# SkyKontrol-2BR.net
KiCad netlist of a schematic drawn in EAGLE
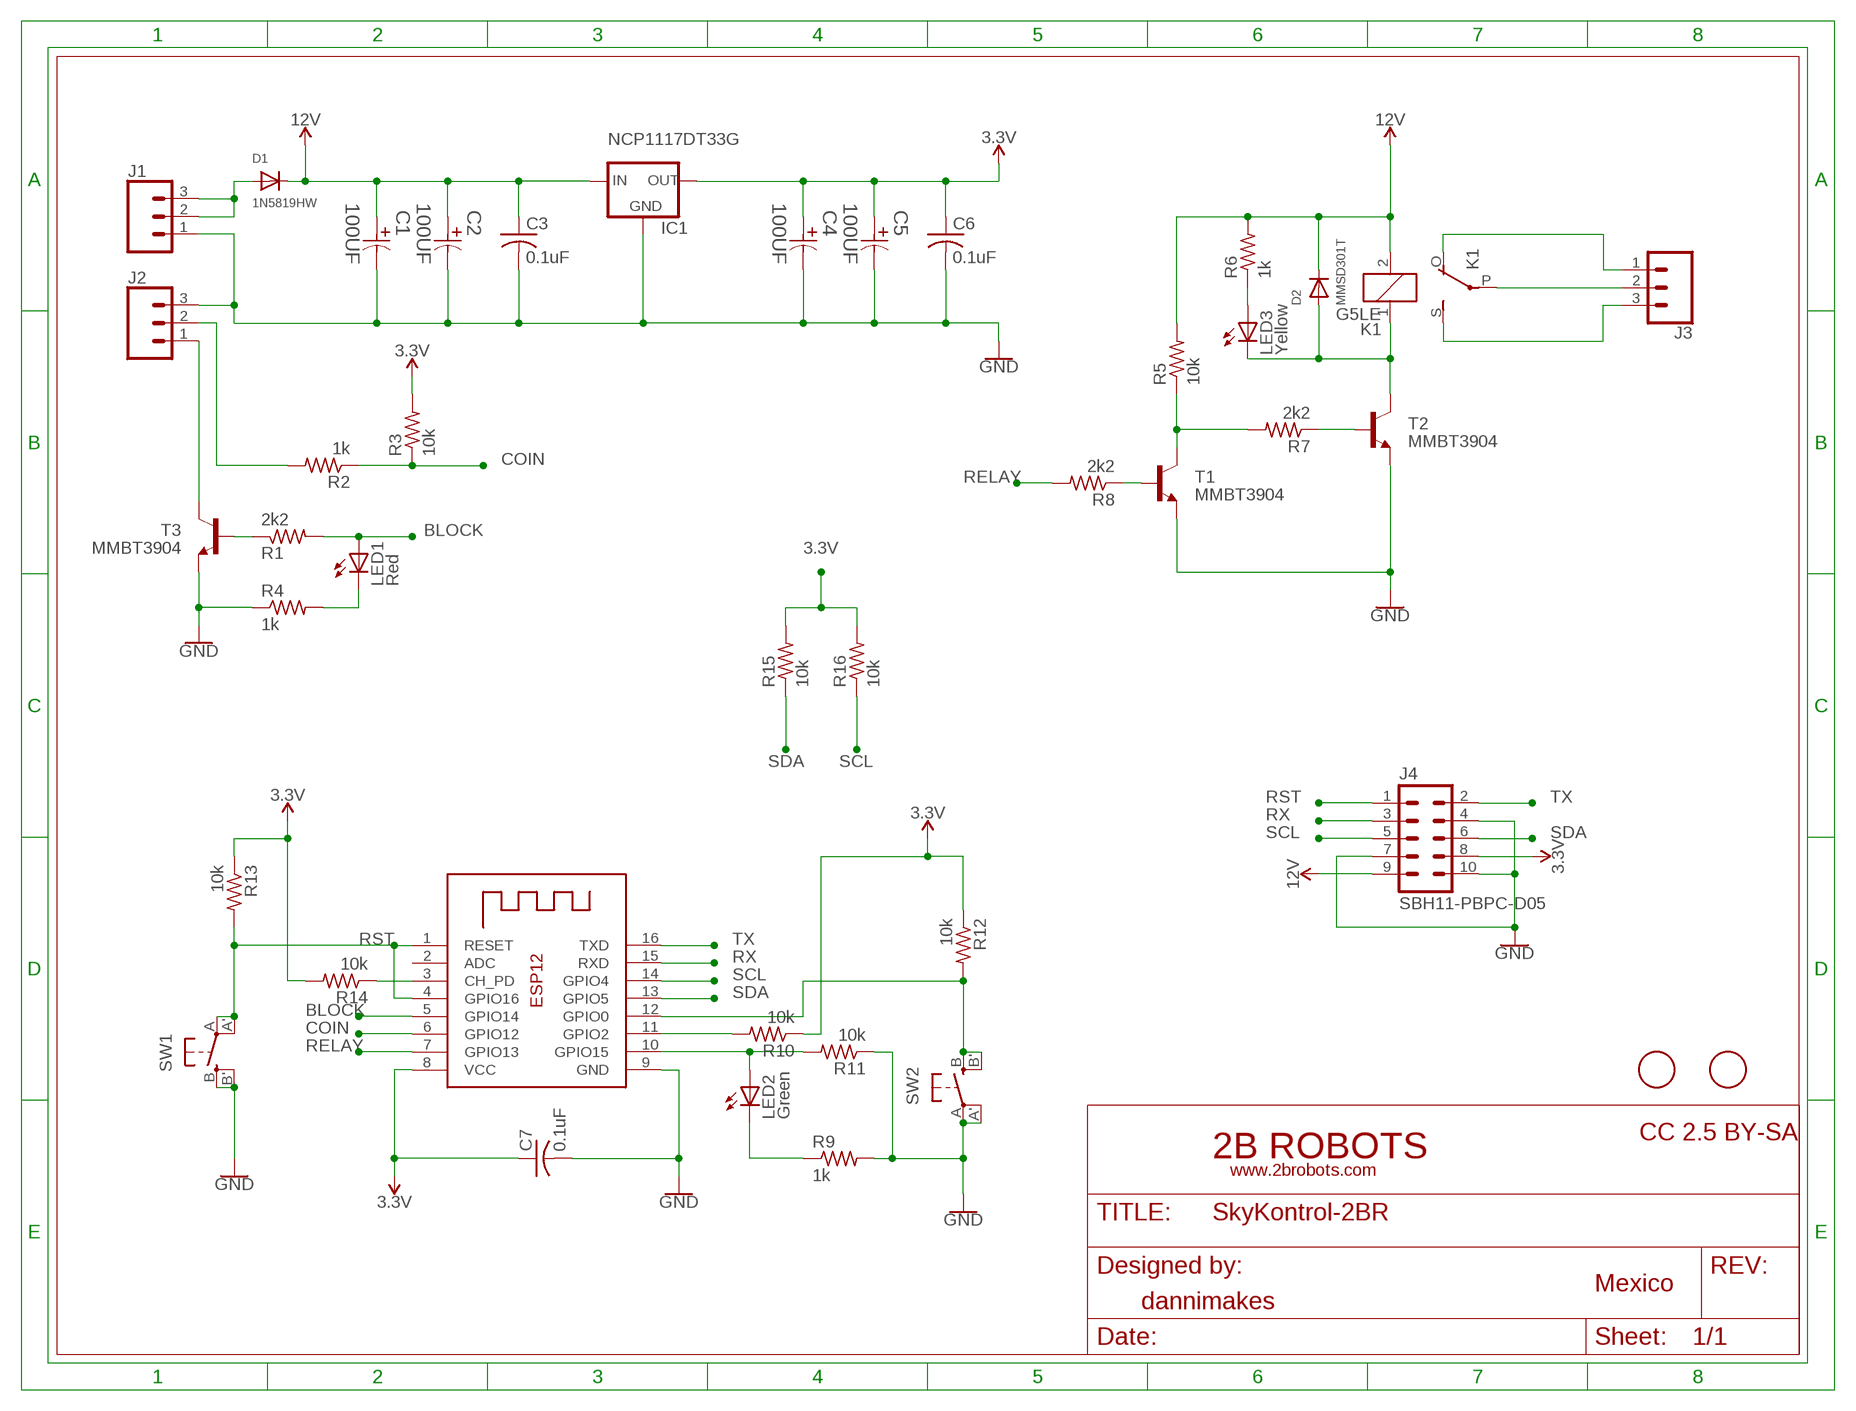
[diagram p0: schematic, sheet 1]

(export (version "E")
  (design (tool "Eeschema 10.0.6"))
  (components
    (comp (ref "C1")
      (value "100UF")
      (footprint "eagle-import:CAPAE660X800N")
      (fields (field (name "MPN") "EEE-HA1E101XP") (field (name "TOLERANCE") "±20 %"))
      (libsource (lib "eagle-import") (part "EEE--CASE-D8HA1E101XP"))
    )
    (comp (ref "C2")
      (value "100UF")
      (footprint "eagle-import:CAPAE660X800N")
      (fields (field (name "MPN") "EEE-HA1E101XP") (field (name "TOLERANCE") "±20 %"))
      (libsource (lib "eagle-import") (part "EEE--CASE-D8HA1E101XP"))
    )
    (comp (ref "C3")
      (value "0.1uF")
      (footprint "eagle-import:C0603K")
      (libsource (lib "eagle-import") (part "C-USC0603K"))
    )
    (comp (ref "C4")
      (value "100UF")
      (footprint "eagle-import:CAPAE660X800N")
      (fields (field (name "MPN") "EEE-HA1E101XP") (field (name "TOLERANCE") "±20 %"))
      (libsource (lib "eagle-import") (part "EEE--CASE-D8HA1E101XP"))
    )
    (comp (ref "C5")
      (value "100UF")
      (footprint "eagle-import:CAPAE660X800N")
      (fields (field (name "MPN") "EEE-HA1E101XP") (field (name "TOLERANCE") "±20 %"))
      (libsource (lib "eagle-import") (part "EEE--CASE-D8HA1E101XP"))
    )
    (comp (ref "C6")
      (value "0.1uF")
      (footprint "eagle-import:C0603K")
      (libsource (lib "eagle-import") (part "C-USC0603K"))
    )
    (comp (ref "C7")
      (value "0.1uF")
      (footprint "eagle-import:C0603K")
      (libsource (lib "eagle-import") (part "C-USC0603K"))
    )
    (comp (ref "D1")
      (value "1N5819HW")
      (footprint "eagle-import:SOD-123")
      (libsource (lib "eagle-import") (part "DIODESOD-123"))
    )
    (comp (ref "D2")
      (value "MMSD301T")
      (footprint "eagle-import:SOD-123")
      (libsource (lib "eagle-import") (part "DIODESOD-123"))
    )
    (comp (ref "IC1")
      (value "NCP1117DT33G")
      (footprint "eagle-import:TO252")
      (libsource (lib "eagle-import") (part "LM1117TO252"))
    )
    (comp (ref "J1")
      (value "CONN_03-SCREW-5MM")
      (footprint "eagle-import:SCREWTERMINAL-5MM-3")
      (libsource (lib "eagle-import") (part "CONN_03-SCREW-5MM"))
    )
    (comp (ref "J2")
      (value "CONN_03-SCREW-5MM")
      (footprint "eagle-import:SCREWTERMINAL-5MM-3")
      (libsource (lib "eagle-import") (part "CONN_03-SCREW-5MM"))
    )
    (comp (ref "J3")
      (value "CONN_03-SCREW-5MM")
      (footprint "eagle-import:SCREWTERMINAL-5MM-3")
      (libsource (lib "eagle-import") (part "CONN_03-SCREW-5MM"))
    )
    (comp (ref "J4")
      (value "SBH11-PBPC-D05")
      (footprint "eagle-import:SBH11-PBPC-D05")
      (libsource (lib "eagle-import") (part "SBH11-PBPC-D05"))
    )
    (comp (ref "K1")
      (value "G5LE")
      (footprint "eagle-import:G5LE")
      (libsource (lib "eagle-import") (part "G5LE"))
    )
    (comp (ref "LED1")
      (value "Red")
      (footprint "eagle-import:CHIPLED_1206")
      (libsource (lib "eagle-import") (part "LEDCHIPLED_1206"))
    )
    (comp (ref "LED2")
      (value "Green")
      (footprint "eagle-import:CHIPLED_1206")
      (libsource (lib "eagle-import") (part "LEDCHIPLED_1206"))
    )
    (comp (ref "LED3")
      (value "Yellow")
      (footprint "eagle-import:CHIPLED_1206")
      (libsource (lib "eagle-import") (part "LEDCHIPLED_1206"))
    )
    (comp (ref "R1")
      (value "2k2")
      (footprint "eagle-import:R0805")
      (libsource (lib "eagle-import") (part "R-US_R0805"))
    )
    (comp (ref "R2")
      (value "1k")
      (footprint "eagle-import:R0805")
      (libsource (lib "eagle-import") (part "R-US_R0805"))
    )
    (comp (ref "R3")
      (value "10k")
      (footprint "eagle-import:R0805")
      (libsource (lib "eagle-import") (part "R-US_R0805"))
    )
    (comp (ref "R4")
      (value "1k")
      (footprint "eagle-import:R0805")
      (libsource (lib "eagle-import") (part "R-US_R0805"))
    )
    (comp (ref "R5")
      (value "10k")
      (footprint "eagle-import:R0805")
      (libsource (lib "eagle-import") (part "R-US_R0805"))
    )
    (comp (ref "R6")
      (value "1k")
      (footprint "eagle-import:R0805")
      (libsource (lib "eagle-import") (part "R-US_R0805"))
    )
    (comp (ref "R7")
      (value "2k2")
      (footprint "eagle-import:R0805")
      (libsource (lib "eagle-import") (part "R-US_R0805"))
    )
    (comp (ref "R8")
      (value "2k2")
      (footprint "eagle-import:R0805")
      (libsource (lib "eagle-import") (part "R-US_R0805"))
    )
    (comp (ref "R9")
      (value "1k")
      (footprint "eagle-import:R0805")
      (libsource (lib "eagle-import") (part "R-US_R0805"))
    )
    (comp (ref "R10")
      (value "10k")
      (footprint "eagle-import:R0805")
      (libsource (lib "eagle-import") (part "R-US_R0805"))
    )
    (comp (ref "R11")
      (value "10k")
      (footprint "eagle-import:R0805")
      (libsource (lib "eagle-import") (part "R-US_R0805"))
    )
    (comp (ref "R12")
      (value "10k")
      (footprint "eagle-import:R0805")
      (libsource (lib "eagle-import") (part "R-US_R0805"))
    )
    (comp (ref "R13")
      (value "10k")
      (footprint "eagle-import:R0805")
      (libsource (lib "eagle-import") (part "R-US_R0805"))
    )
    (comp (ref "R14")
      (value "10k")
      (footprint "eagle-import:R0805")
      (libsource (lib "eagle-import") (part "R-US_R0805"))
    )
    (comp (ref "R15")
      (value "10k")
      (footprint "eagle-import:R0805")
      (libsource (lib "eagle-import") (part "R-US_R0805"))
    )
    (comp (ref "R16")
      (value "10k")
      (footprint "eagle-import:R0805")
      (libsource (lib "eagle-import") (part "R-US_R0805"))
    )
    (comp (ref "SW1")
      (value "SPST_TACT-EVQQ2")
      (footprint "eagle-import:EVQ-Q2")
      (libsource (lib "eagle-import") (part "SPST_TACT-EVQQ2"))
    )
    (comp (ref "SW2")
      (value "SPST_TACT-EVQQ2")
      (footprint "eagle-import:EVQ-Q2")
      (libsource (lib "eagle-import") (part "SPST_TACT-EVQQ2"))
    )
    (comp (ref "T1")
      (value "MMBT3904")
      (footprint "eagle-import:SOT23-BEC")
      (libsource (lib "eagle-import") (part "-NPN-SOT23-BECMMBT3904LT1"))
    )
    (comp (ref "T2")
      (value "MMBT3904")
      (footprint "eagle-import:SOT23-BEC")
      (libsource (lib "eagle-import") (part "-NPN-SOT23-BECMMBT3904LT1"))
    )
    (comp (ref "T3")
      (value "MMBT3904")
      (footprint "eagle-import:SOT23-BEC")
      (libsource (lib "eagle-import") (part "-NPN-SOT23-BECMMBT3904LT1"))
    )
    (comp (ref "U$1")
      (value "FIDUCIAL")
      (footprint "eagle-import:FIDUCIAL_1MM")
      (libsource (lib "eagle-import") (part "FIDUCIAL"))
    )
    (comp (ref "U$2")
      (value "FIDUCIAL")
      (footprint "eagle-import:FIDUCIAL_1MM")
      (libsource (lib "eagle-import") (part "FIDUCIAL"))
    )
    (comp (ref "X1")
      (value "ESP-12")
      (footprint "eagle-import:ESP-12")
      (libsource (lib "eagle-import") (part "ESP-12"))
    )
  )
  (nets
    (net (code "1") (name "/BLOCK") (class "Default")
      (node (ref "LED1") (pin "A") (pinfunction "A_A") (pintype "passive"))
      (node (ref "R1") (pin "2") (pinfunction "2_2") (pintype "passive"))
      (node (ref "X1") (pin "5") (pinfunction "GPIO14_5") (pintype "bidirectional"))
    )
    (net (code "2") (name "/COIN") (class "Default")
      (node (ref "R2") (pin "1") (pinfunction "1_1") (pintype "passive"))
      (node (ref "R3") (pin "1") (pinfunction "1_1") (pintype "passive"))
      (node (ref "X1") (pin "6") (pinfunction "GPIO12_6") (pintype "bidirectional"))
    )
    (net (code "3") (name "/RELAY") (class "Default")
      (node (ref "R8") (pin "2") (pinfunction "2_2") (pintype "passive"))
      (node (ref "X1") (pin "7") (pinfunction "GPIO13_7") (pintype "bidirectional"))
    )
    (net (code "4") (name "/RST") (class "Default")
      (node (ref "J4") (pin "1") (pinfunction "1_1") (pintype "passive"))
      (node (ref "R13") (pin "2") (pinfunction "2_2") (pintype "passive"))
      (node (ref "SW1") (pin "A") (pinfunction "P_A") (pintype "passive"))
      (node (ref "SW1") (pin "A'") (pinfunction "P1_A'") (pintype "passive"))
      (node (ref "X1") (pin "1") (pinfunction "RESET_1") (pintype "input"))
      (node (ref "X1") (pin "4") (pinfunction "GPIO16_4") (pintype "bidirectional"))
    )
    (net (code "5") (name "/RX") (class "Default")
      (node (ref "J4") (pin "3") (pinfunction "3_3") (pintype "passive"))
      (node (ref "X1") (pin "15") (pinfunction "RXD_15") (pintype "input"))
    )
    (net (code "6") (name "/SCL") (class "Default")
      (node (ref "J4") (pin "5") (pinfunction "5_5") (pintype "passive"))
      (node (ref "R16") (pin "1") (pinfunction "1_1") (pintype "passive"))
      (node (ref "X1") (pin "14") (pinfunction "GPIO4_14") (pintype "bidirectional"))
    )
    (net (code "7") (name "/SDA") (class "Default")
      (node (ref "J4") (pin "6") (pinfunction "6_6") (pintype "passive"))
      (node (ref "R15") (pin "1") (pinfunction "1_1") (pintype "passive"))
      (node (ref "X1") (pin "13") (pinfunction "GPIO5_13") (pintype "bidirectional"))
    )
    (net (code "8") (name "/TX") (class "Default")
      (node (ref "J4") (pin "2") (pinfunction "2_2") (pintype "passive"))
      (node (ref "X1") (pin "16") (pinfunction "TXD_16") (pintype "output"))
    )
    (net (code "9") (name "3.3V") (class "Default")
      (node (ref "C4") (pin "1") (pinfunction "1_1") (pintype "passive"))
      (node (ref "C5") (pin "1") (pinfunction "1_1") (pintype "passive"))
      (node (ref "C6") (pin "1") (pinfunction "1_1") (pintype "passive"))
      (node (ref "C7") (pin "1") (pinfunction "1_1") (pintype "passive"))
      (node (ref "IC1") (pin "3") (pinfunction "OUT_3") (pintype "passive"))
      (node (ref "J4") (pin "8") (pinfunction "8_8") (pintype "passive"))
      (node (ref "R10") (pin "1") (pinfunction "1_1") (pintype "passive"))
      (node (ref "R12") (pin "1") (pinfunction "1_1") (pintype "passive"))
      (node (ref "R13") (pin "1") (pinfunction "1_1") (pintype "passive"))
      (node (ref "R14") (pin "2") (pinfunction "2_2") (pintype "passive"))
      (node (ref "R15") (pin "2") (pinfunction "2_2") (pintype "passive"))
      (node (ref "R16") (pin "2") (pinfunction "2_2") (pintype "passive"))
      (node (ref "R3") (pin "2") (pinfunction "2_2") (pintype "passive"))
      (node (ref "X1") (pin "8") (pinfunction "VCC_8") (pintype "power_in"))
    )
    (net (code "10") (name "12V") (class "Default")
      (node (ref "C1") (pin "1") (pinfunction "1_1") (pintype "passive"))
      (node (ref "C2") (pin "1") (pinfunction "1_1") (pintype "passive"))
      (node (ref "C3") (pin "1") (pinfunction "1_1") (pintype "passive"))
      (node (ref "D1") (pin "C") (pinfunction "C_C") (pintype "passive"))
      (node (ref "D2") (pin "C") (pinfunction "C_C") (pintype "passive"))
      (node (ref "IC1") (pin "2") (pinfunction "IN_2") (pintype "input"))
      (node (ref "J4") (pin "9") (pinfunction "9_9") (pintype "passive"))
      (node (ref "K1") (pin "2") (pinfunction "2_2") (pintype "passive"))
      (node (ref "R5") (pin "2") (pinfunction "2_2") (pintype "passive"))
      (node (ref "R6") (pin "2") (pinfunction "2_2") (pintype "passive"))
    )
    (net (code "11") (name "GND") (class "Default")
      (node (ref "C1") (pin "2") (pinfunction "2_2") (pintype "passive"))
      (node (ref "C2") (pin "2") (pinfunction "2_2") (pintype "passive"))
      (node (ref "C3") (pin "2") (pinfunction "2_2") (pintype "passive"))
      (node (ref "C4") (pin "2") (pinfunction "2_2") (pintype "passive"))
      (node (ref "C5") (pin "2") (pinfunction "2_2") (pintype "passive"))
      (node (ref "C6") (pin "2") (pinfunction "2_2") (pintype "passive"))
      (node (ref "C7") (pin "2") (pinfunction "2_2") (pintype "passive"))
      (node (ref "IC1") (pin "1") (pinfunction "GND_1") (pintype "input"))
      (node (ref "J1") (pin "1") (pinfunction "1_1") (pintype "passive"))
      (node (ref "J2") (pin "3") (pinfunction "3_3") (pintype "passive"))
      (node (ref "J4") (pin "10") (pinfunction "10_10") (pintype "passive"))
      (node (ref "J4") (pin "4") (pinfunction "4_4") (pintype "passive"))
      (node (ref "J4") (pin "7") (pinfunction "7_7") (pintype "passive"))
      (node (ref "R11") (pin "1") (pinfunction "1_1") (pintype "passive"))
      (node (ref "R4") (pin "1") (pinfunction "1_1") (pintype "passive"))
      (node (ref "R9") (pin "2") (pinfunction "2_2") (pintype "passive"))
      (node (ref "SW1") (pin "B") (pinfunction "S_B") (pintype "passive"))
      (node (ref "SW1") (pin "B'") (pinfunction "S1_B'") (pintype "passive"))
      (node (ref "SW2") (pin "A") (pinfunction "P_A") (pintype "passive"))
      (node (ref "SW2") (pin "A'") (pinfunction "P1_A'") (pintype "passive"))
      (node (ref "T1") (pin "E") (pinfunction "E_E") (pintype "passive"))
      (node (ref "T2") (pin "E") (pinfunction "E_E") (pintype "passive"))
      (node (ref "T3") (pin "E") (pinfunction "E_E") (pintype "passive"))
      (node (ref "X1") (pin "9") (pinfunction "GND_9") (pintype "power_in"))
    )
    (net (code "12") (name "Net-(D1-PadA)") (class "Default")
      (node (ref "D1") (pin "A") (pinfunction "A_A") (pintype "passive"))
      (node (ref "J1") (pin "2") (pinfunction "2_2") (pintype "passive"))
      (node (ref "J1") (pin "3") (pinfunction "3_3") (pintype "passive"))
    )
    (net (code "13") (name "Net-(D2-PadA)") (class "Default")
      (node (ref "D2") (pin "A") (pinfunction "A_A") (pintype "passive"))
      (node (ref "K1") (pin "1") (pinfunction "1_1") (pintype "passive"))
      (node (ref "LED3") (pin "C") (pinfunction "C_C") (pintype "passive"))
      (node (ref "T2") (pin "C") (pinfunction "C_C") (pintype "passive"))
    )
    (net (code "14") (name "Net-(J2-Pad1)") (class "Default")
      (node (ref "J2") (pin "1") (pinfunction "1_1") (pintype "passive"))
      (node (ref "T3") (pin "C") (pinfunction "C_C") (pintype "passive"))
    )
    (net (code "15") (name "Net-(J2-Pad2)") (class "Default")
      (node (ref "J2") (pin "2") (pinfunction "2_2") (pintype "passive"))
      (node (ref "R2") (pin "2") (pinfunction "2_2") (pintype "passive"))
    )
    (net (code "16") (name "Net-(J3-Pad1)") (class "Default")
      (node (ref "J3") (pin "1") (pinfunction "1_1") (pintype "passive"))
      (node (ref "K1") (pin "O") (pinfunction "O_O") (pintype "passive"))
    )
    (net (code "17") (name "Net-(J3-Pad2)") (class "Default")
      (node (ref "J3") (pin "2") (pinfunction "2_2") (pintype "passive"))
      (node (ref "K1") (pin "P") (pinfunction "P_P") (pintype "passive"))
    )
    (net (code "18") (name "Net-(J3-Pad3)") (class "Default")
      (node (ref "J3") (pin "3") (pinfunction "3_3") (pintype "passive"))
      (node (ref "K1") (pin "S") (pinfunction "S_S") (pintype "passive"))
    )
    (net (code "19") (name "Net-(LED1-PadC)") (class "Default")
      (node (ref "LED1") (pin "C") (pinfunction "C_C") (pintype "passive"))
      (node (ref "R4") (pin "2") (pinfunction "2_2") (pintype "passive"))
    )
    (net (code "20") (name "Net-(LED2-PadC)") (class "Default")
      (node (ref "LED2") (pin "C") (pinfunction "C_C") (pintype "passive"))
      (node (ref "R9") (pin "1") (pinfunction "1_1") (pintype "passive"))
    )
    (net (code "21") (name "Net-(LED3-PadA)") (class "Default")
      (node (ref "LED3") (pin "A") (pinfunction "A_A") (pintype "passive"))
      (node (ref "R6") (pin "1") (pinfunction "1_1") (pintype "passive"))
    )
    (net (code "22") (name "Net-(R1-Pad1)") (class "Default")
      (node (ref "R1") (pin "1") (pinfunction "1_1") (pintype "passive"))
      (node (ref "T3") (pin "B") (pinfunction "B_B") (pintype "passive"))
    )
    (net (code "23") (name "Net-(R5-Pad1)") (class "Default")
      (node (ref "R5") (pin "1") (pinfunction "1_1") (pintype "passive"))
      (node (ref "R7") (pin "2") (pinfunction "2_2") (pintype "passive"))
      (node (ref "T1") (pin "C") (pinfunction "C_C") (pintype "passive"))
    )
    (net (code "24") (name "Net-(R7-Pad1)") (class "Default")
      (node (ref "R7") (pin "1") (pinfunction "1_1") (pintype "passive"))
      (node (ref "T2") (pin "B") (pinfunction "B_B") (pintype "passive"))
    )
    (net (code "25") (name "Net-(R8-Pad1)") (class "Default")
      (node (ref "R8") (pin "1") (pinfunction "1_1") (pintype "passive"))
      (node (ref "T1") (pin "B") (pinfunction "B_B") (pintype "passive"))
    )
    (net (code "26") (name "Net-(SW2-S)") (class "Default")
      (node (ref "R12") (pin "2") (pinfunction "2_2") (pintype "passive"))
      (node (ref "SW2") (pin "B") (pinfunction "S_B") (pintype "passive"))
      (node (ref "SW2") (pin "B'") (pinfunction "S1_B'") (pintype "passive"))
      (node (ref "X1") (pin "12") (pinfunction "GPIO0_12") (pintype "bidirectional"))
    )
    (net (code "27") (name "Net-(X1-CH_PD)") (class "Default")
      (node (ref "R14") (pin "1") (pinfunction "1_1") (pintype "passive"))
      (node (ref "X1") (pin "3") (pinfunction "CH_PD_3") (pintype "input"))
    )
    (net (code "28") (name "Net-(X1-GPIO2)") (class "Default")
      (node (ref "R10") (pin "2") (pinfunction "2_2") (pintype "passive"))
      (node (ref "X1") (pin "11") (pinfunction "GPIO2_11") (pintype "bidirectional"))
    )
    (net (code "29") (name "Net-(X1-GPIO15)") (class "Default")
      (node (ref "LED2") (pin "A") (pinfunction "A_A") (pintype "passive"))
      (node (ref "R11") (pin "2") (pinfunction "2_2") (pintype "passive"))
      (node (ref "X1") (pin "10") (pinfunction "GPIO15_10") (pintype "bidirectional"))
    )
    (net (code "30") (name "unconnected-(X1-ADC-Pad2)") (class "Default")
      (node (ref "X1") (pin "2") (pinfunction "ADC_2") (pintype "passive"))
    )
  )
)
